# ADCConvert.net
KiCad netlist of a schematic drawn in Altium Designer
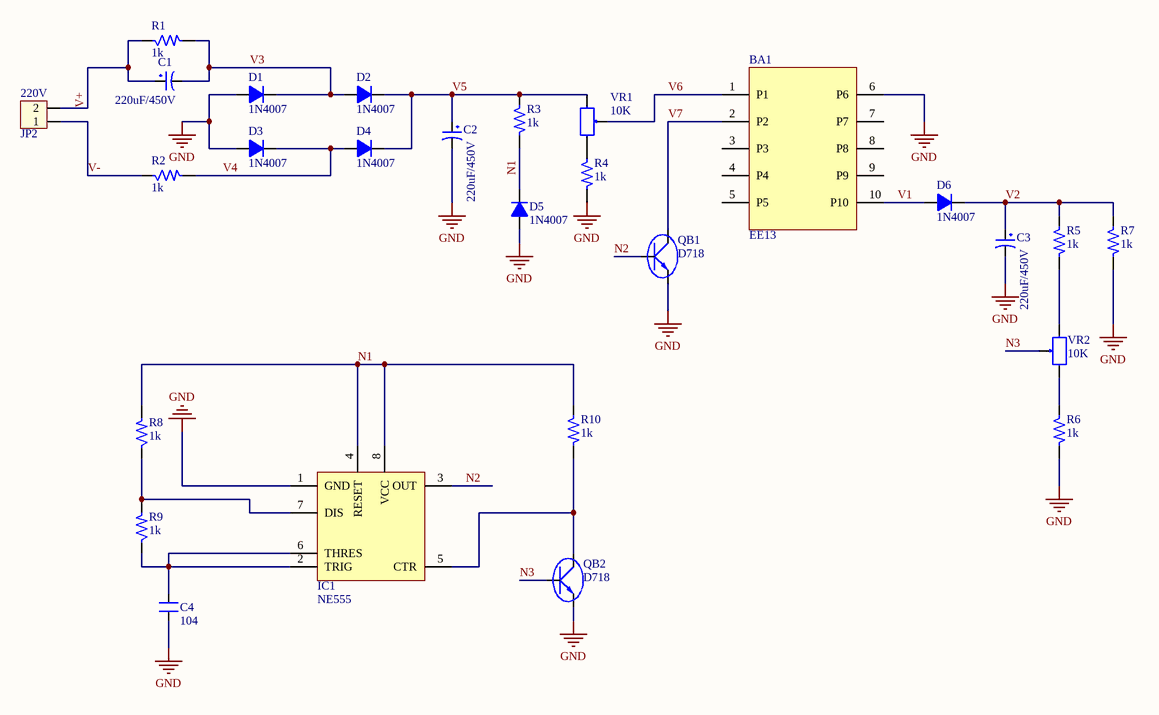
[diagram p0: ADCConvert.SchDoc]

(export (version "E")
  (design (tool "Eeschema 10.0.6"))
  (components
    (comp (ref "220V")
      (value "JP2")
      (footprint "CON2")
      (description "Connector 2")
      (libsource (lib "syhaunguyen") (part "Con2"))
    )
    (comp (ref "BA1")
      (value "EE13")
      (footprint "EE1BA")
      (libsource (lib "Nupakachi") (part "EE13-Tranformer"))
    )
    (comp (ref "C1")
      (value "220uF/450V")
      (footprint "CP1/2")
      (description "Cap 10000uF/63V")
      (libsource (lib "syhaunguyen") (part "CP9"))
    )
    (comp (ref "C2")
      (value "220uF/450V")
      (footprint "CP1.5/3.4")
      (description "Cap 10000uF/63V")
      (libsource (lib "") (part "CP9_1"))
    )
    (comp (ref "C3")
      (value "220uF/450V")
      (footprint "CP1.5/3.4")
      (description "Cap 10000uF/63V")
      (libsource (lib "") (part "CP9_1"))
    )
    (comp (ref "C4")
      (value "104")
      (footprint "CP1/2")
      (description "Cap np 104 => 105pF")
      (libsource (lib "syhaunguyen") (part "CN2"))
    )
    (comp (ref "D1")
      (value "1N4007")
      (footprint "D1A")
      (description "Diode 1A")
      (libsource (lib "syhaunguyen") (part "D1A"))
    )
    (comp (ref "D2")
      (value "1N4007")
      (footprint "D1A")
      (description "Diode 1A")
      (libsource (lib "syhaunguyen") (part "D1A"))
    )
    (comp (ref "D3")
      (value "1N4007")
      (footprint "D1A")
      (description "Diode 1A")
      (libsource (lib "syhaunguyen") (part "D1A"))
    )
    (comp (ref "D4")
      (value "1N4007")
      (footprint "D1A")
      (description "Diode 1A")
      (libsource (lib "syhaunguyen") (part "D1A"))
    )
    (comp (ref "D5")
      (value "1N4007")
      (footprint "D1A")
      (description "Diode 1A")
      (libsource (lib "syhaunguyen") (part "D1A"))
    )
    (comp (ref "D6")
      (value "1N4007")
      (footprint "D1A")
      (description "Diode 1A")
      (libsource (lib "syhaunguyen") (part "D1A"))
    )
    (comp (ref "IC1") (value "NE555") (footprint "DIP8/W0.3K") (libsource (lib "Nupakachi") (part "NE555")))
    (comp (ref "QB1")
      (value "D718")
      (footprint "QTO-220T")
      (description "Transistor Power Supply")
      (libsource (lib "syhaunguyen") (part "D718"))
    )
    (comp (ref "QB2")
      (value "D718")
      (footprint "QTO-220T")
      (description "Transistor Power Supply")
      (libsource (lib "syhaunguyen") (part "D718"))
    )
    (comp (ref "R1")
      (value "1k")
      (footprint "R1/2W")
      (description "Resistor 1/4W")
      (libsource (lib "syhaunguyen") (part "R"))
    )
    (comp (ref "R2")
      (value "1k")
      (footprint "R1/2W")
      (description "Resistor 1/4W")
      (libsource (lib "syhaunguyen") (part "R"))
    )
    (comp (ref "R3")
      (value "1k")
      (footprint "R1/2W")
      (description "Resistor 1/4W")
      (libsource (lib "syhaunguyen") (part "R"))
    )
    (comp (ref "R4")
      (value "1k")
      (footprint "R1/2W")
      (description "Resistor 1/4W")
      (libsource (lib "syhaunguyen") (part "R"))
    )
    (comp (ref "R5")
      (value "1k")
      (footprint "R1/2W")
      (description "Resistor 1/4W")
      (libsource (lib "syhaunguyen") (part "R"))
    )
    (comp (ref "R6")
      (value "1k")
      (footprint "R1/2W")
      (description "Resistor 1/4W")
      (libsource (lib "syhaunguyen") (part "R"))
    )
    (comp (ref "R7")
      (value "1k")
      (footprint "R1/2W")
      (description "Resistor 1/4W")
      (libsource (lib "syhaunguyen") (part "R"))
    )
    (comp (ref "R8")
      (value "1k")
      (footprint "R1/2W")
      (description "Resistor 1/4W")
      (libsource (lib "syhaunguyen") (part "R"))
    )
    (comp (ref "R9")
      (value "1k")
      (footprint "R1/2W")
      (description "Resistor 1/4W")
      (libsource (lib "syhaunguyen") (part "R"))
    )
    (comp (ref "R10")
      (value "1k")
      (footprint "R1/2W")
      (description "Resistor 1/4W")
      (libsource (lib "syhaunguyen") (part "R"))
    )
    (comp (ref "VR1")
      (value "10K")
      (footprint "VR")
      (description "Var Resistor")
      (libsource (lib "syhaunguyen") (part "VR"))
    )
    (comp (ref "VR2")
      (value "10K")
      (footprint "VR")
      (description "Var Resistor")
      (libsource (lib "syhaunguyen") (part "VR"))
    )
  )
  (nets
    (net (code "1") (name "/N1") (class "Default")
      (node (ref "D5") (pin "2") (pinfunction "K_2") (pintype "passive"))
      (node (ref "IC1") (pin "4") (pinfunction "RESET_4") (pintype "power_in"))
      (node (ref "IC1") (pin "8") (pinfunction "VCC_8") (pintype "passive"))
      (node (ref "R10") (pin "1") (pinfunction "1_1") (pintype "passive"))
      (node (ref "R3") (pin "2") (pinfunction "2_2") (pintype "passive"))
      (node (ref "R8") (pin "2") (pinfunction "2_2") (pintype "passive"))
    )
    (net (code "2") (name "/N2") (class "Default")
      (node (ref "IC1") (pin "3") (pinfunction "OUT_3") (pintype "power_in"))
      (node (ref "QB1") (pin "1") (pinfunction "B_1") (pintype "passive"))
    )
    (net (code "3") (name "/N3") (class "Default")
      (node (ref "QB2") (pin "1") (pinfunction "B_1") (pintype "passive"))
      (node (ref "VR2") (pin "2") (pinfunction "2_2") (pintype "passive"))
    )
    (net (code "4") (name "/V+") (class "Default")
      (node (ref "220V") (pin "2") (pinfunction "2_2") (pintype "passive"))
      (node (ref "C1") (pin "1") (pinfunction "1_1") (pintype "passive"))
      (node (ref "R1") (pin "1") (pinfunction "1_1") (pintype "passive"))
    )
    (net (code "5") (name "/V-") (class "Default")
      (node (ref "220V") (pin "1") (pinfunction "1_1") (pintype "passive"))
      (node (ref "R2") (pin "1") (pinfunction "1_1") (pintype "passive"))
    )
    (net (code "6") (name "/V1") (class "Default")
      (node (ref "BA1") (pin "10") (pinfunction "P10_10") (pintype "passive"))
      (node (ref "D6") (pin "1") (pinfunction "A_1") (pintype "passive"))
    )
    (net (code "7") (name "/V2") (class "Default")
      (node (ref "C3") (pin "1") (pinfunction "1_1") (pintype "passive"))
      (node (ref "D6") (pin "2") (pinfunction "K_2") (pintype "passive"))
      (node (ref "R5") (pin "1") (pinfunction "1_1") (pintype "passive"))
      (node (ref "R7") (pin "1") (pinfunction "1_1") (pintype "passive"))
    )
    (net (code "8") (name "/V3") (class "Default")
      (node (ref "C1") (pin "2") (pinfunction "2_2") (pintype "passive"))
      (node (ref "D1") (pin "2") (pinfunction "K_2") (pintype "passive"))
      (node (ref "D2") (pin "1") (pinfunction "A_1") (pintype "passive"))
      (node (ref "R1") (pin "2") (pinfunction "2_2") (pintype "passive"))
    )
    (net (code "9") (name "/V4") (class "Default")
      (node (ref "D3") (pin "2") (pinfunction "K_2") (pintype "passive"))
      (node (ref "D4") (pin "1") (pinfunction "A_1") (pintype "passive"))
      (node (ref "R2") (pin "2") (pinfunction "2_2") (pintype "passive"))
    )
    (net (code "10") (name "/V5") (class "Default")
      (node (ref "C2") (pin "1") (pinfunction "1_1") (pintype "passive"))
      (node (ref "D2") (pin "2") (pinfunction "K_2") (pintype "passive"))
      (node (ref "D4") (pin "2") (pinfunction "K_2") (pintype "passive"))
      (node (ref "R3") (pin "1") (pinfunction "1_1") (pintype "passive"))
      (node (ref "VR1") (pin "1") (pinfunction "1_1") (pintype "passive"))
    )
    (net (code "11") (name "/V6") (class "Default")
      (node (ref "BA1") (pin "1") (pinfunction "P1_1") (pintype "passive"))
      (node (ref "VR1") (pin "2") (pinfunction "2_2") (pintype "passive"))
    )
    (net (code "12") (name "/V7") (class "Default")
      (node (ref "BA1") (pin "2") (pinfunction "P2_2") (pintype "passive"))
      (node (ref "QB1") (pin "2") (pinfunction "C_2") (pintype "passive"))
    )
    (net (code "13") (name "GND") (class "Default")
      (node (ref "BA1") (pin "6") (pinfunction "P6_6") (pintype "passive"))
      (node (ref "C2") (pin "2") (pinfunction "2_2") (pintype "passive"))
      (node (ref "C3") (pin "2") (pinfunction "2_2") (pintype "passive"))
      (node (ref "C4") (pin "1") (pinfunction "1_1") (pintype "passive"))
      (node (ref "D1") (pin "1") (pinfunction "A_1") (pintype "passive"))
      (node (ref "D3") (pin "1") (pinfunction "A_1") (pintype "passive"))
      (node (ref "D5") (pin "1") (pinfunction "A_1") (pintype "passive"))
      (node (ref "IC1") (pin "1") (pinfunction "GND_1") (pintype "power_in"))
      (node (ref "QB1") (pin "3") (pinfunction "E_3") (pintype "passive"))
      (node (ref "QB2") (pin "3") (pinfunction "E_3") (pintype "passive"))
      (node (ref "R4") (pin "2") (pinfunction "2_2") (pintype "passive"))
      (node (ref "R6") (pin "2") (pinfunction "2_2") (pintype "passive"))
      (node (ref "R7") (pin "2") (pinfunction "2_2") (pintype "passive"))
    )
    (net (code "14") (name "Net-(IC1-CTR)") (class "Default")
      (node (ref "IC1") (pin "5") (pinfunction "CTR_5") (pintype "passive"))
      (node (ref "QB2") (pin "2") (pinfunction "C_2") (pintype "passive"))
      (node (ref "R10") (pin "2") (pinfunction "2_2") (pintype "passive"))
    )
    (net (code "15") (name "Net-(IC1-DIS)") (class "Default")
      (node (ref "IC1") (pin "7") (pinfunction "DIS_7") (pintype "passive"))
      (node (ref "R8") (pin "1") (pinfunction "1_1") (pintype "passive"))
      (node (ref "R9") (pin "2") (pinfunction "2_2") (pintype "passive"))
    )
    (net (code "16") (name "Net-(IC1-THRES)") (class "Default")
      (node (ref "C4") (pin "2") (pinfunction "2_2") (pintype "passive"))
      (node (ref "IC1") (pin "2") (pinfunction "TRIG_2") (pintype "passive"))
      (node (ref "IC1") (pin "6") (pinfunction "THRES_6") (pintype "passive"))
      (node (ref "R9") (pin "1") (pinfunction "1_1") (pintype "passive"))
    )
    (net (code "17") (name "Net-(R4-Pad1)") (class "Default")
      (node (ref "R4") (pin "1") (pinfunction "1_1") (pintype "passive"))
      (node (ref "VR1") (pin "3") (pinfunction "3_3") (pintype "passive"))
    )
    (net (code "18") (name "Net-(R5-Pad2)") (class "Default")
      (node (ref "R5") (pin "2") (pinfunction "2_2") (pintype "passive"))
      (node (ref "VR2") (pin "3") (pinfunction "3_3") (pintype "passive"))
    )
    (net (code "19") (name "Net-(R6-Pad1)") (class "Default")
      (node (ref "R6") (pin "1") (pinfunction "1_1") (pintype "passive"))
      (node (ref "VR2") (pin "1") (pinfunction "1_1") (pintype "passive"))
    )
    (net (code "20") (name "unconnected-(BA1-P3-Pad3)") (class "Default")
      (node (ref "BA1") (pin "3") (pinfunction "P3_3") (pintype "passive"))
    )
    (net (code "21") (name "unconnected-(BA1-P4-Pad4)") (class "Default")
      (node (ref "BA1") (pin "4") (pinfunction "P4_4") (pintype "passive"))
    )
    (net (code "22") (name "unconnected-(BA1-P5-Pad5)") (class "Default")
      (node (ref "BA1") (pin "5") (pinfunction "P5_5") (pintype "passive"))
    )
    (net (code "23") (name "unconnected-(BA1-P7-Pad7)") (class "Default")
      (node (ref "BA1") (pin "7") (pinfunction "P7_7") (pintype "passive"))
    )
    (net (code "24") (name "unconnected-(BA1-P8-Pad8)") (class "Default")
      (node (ref "BA1") (pin "8") (pinfunction "P8_8") (pintype "passive"))
    )
    (net (code "25") (name "unconnected-(BA1-P9-Pad9)") (class "Default")
      (node (ref "BA1") (pin "9") (pinfunction "P9_9") (pintype "passive"))
    )
  )
)
